# ts2068Interface.net
KiCad netlist of a schematic drawn in Altium Designer
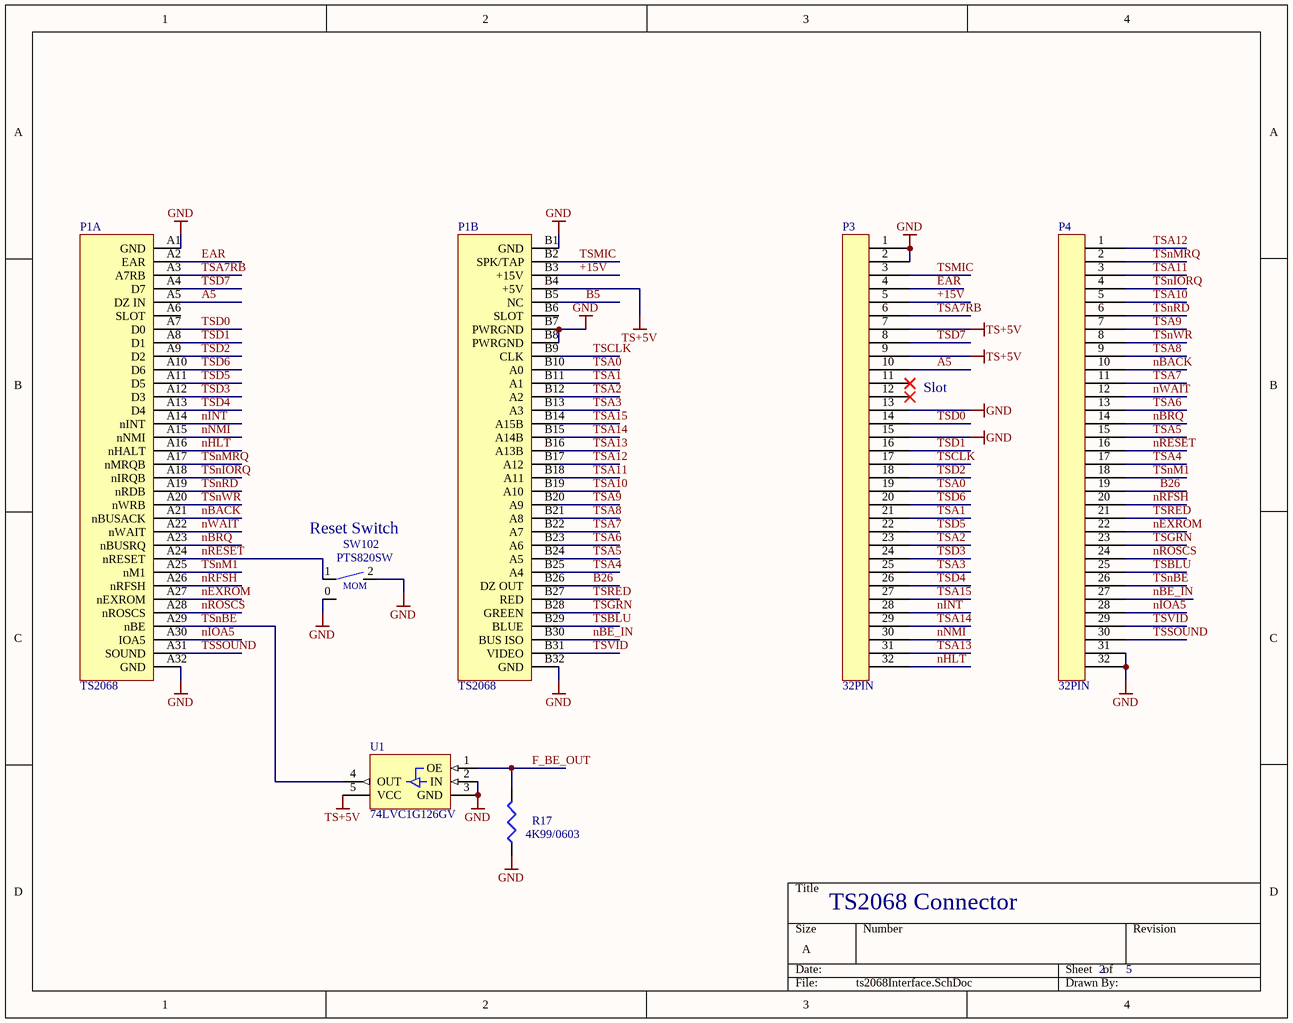
[diagram p0: ts2068Interface.SchDoc]

(export (version "E")
  (design (tool "Eeschema 10.0.6"))
  (components
    (comp (ref "P1") (value "TS2068") (footprint "TS2068A") (libsource (lib "Modules") (part "TS2068")))
    (comp (ref "P3") (value "32PIN") (footprint "IDC32") (libsource (lib "Connectors") (part "32PIN")))
    (comp (ref "P4") (value "32PIN") (footprint "IDC32") (libsource (lib "Connectors") (part "32PIN")))
    (comp (ref "R17")
      (value "4K99/0603")
      (footprint "0603")
      (description "RES 4.99K OHM 1/10W 1% 0603 SMD")
      (fields (field (name "MFG") "Dale/Vishay"))
      (libsource (lib "C64Interface") (part "4K99/0603"))
    )
    (comp (ref "SW102")
      (value "PTS820SW")
      (footprint "PTS820")
      (description "Tactile Switch SPST-NO Top Actuated Surface Mount")
      (fields (field (name "MFG") "C&K"))
      (libsource (lib "Misc") (part "PTS820SW"))
    )
    (comp (ref "U1")
      (value "74LVC1G126GV")
      (footprint "SOT23-5")
      (description "Buffer, Non-Inverting 1 Element 1 Bit per Element 3-State Output SC-74A")
      (fields (field (name "MFG") "Nexperia"))
      (libsource (lib "DigitalIC") (part "74LVC1G126GV"))
    )
  )
  (nets
    (net (code "1") (name "/+15V") (class "Default")
      (node (ref "P1") (pin "B3") (pinfunction "+15V_B3") (pintype "passive"))
      (node (ref "P3") (pin "5") (pintype "passive"))
    )
    (net (code "2") (name "/A5") (class "Default")
      (node (ref "P1") (pin "A5") (pinfunction "DZ_IN_A5") (pintype "passive"))
      (node (ref "P3") (pin "10") (pintype "passive"))
    )
    (net (code "3") (name "/B5") (class "Default")
      (node (ref "P1") (pin "B5") (pinfunction "NC_B5") (pintype "passive"))
    )
    (net (code "4") (name "/B26") (class "Default")
      (node (ref "P1") (pin "B26") (pinfunction "DZ_OUT_B26") (pintype "passive"))
      (node (ref "P4") (pin "19") (pintype "passive"))
    )
    (net (code "5") (name "/EAR") (class "Default")
      (node (ref "P1") (pin "A2") (pinfunction "EAR_A2") (pintype "passive"))
      (node (ref "P3") (pin "4") (pintype "passive"))
    )
    (net (code "6") (name "/F_BE_OUT") (class "Default")
      (node (ref "R17") (pin "2") (pintype "passive"))
      (node (ref "U1") (pin "1") (pinfunction "OE_1") (pintype "input"))
    )
    (net (code "7") (name "/TSA0") (class "Default")
      (node (ref "P1") (pin "B10") (pinfunction "A0_B10") (pintype "passive"))
      (node (ref "P3") (pin "19") (pintype "passive"))
    )
    (net (code "8") (name "/TSA1") (class "Default")
      (node (ref "P1") (pin "B11") (pinfunction "A1_B11") (pintype "passive"))
      (node (ref "P3") (pin "21") (pintype "passive"))
    )
    (net (code "9") (name "/TSA2") (class "Default")
      (node (ref "P1") (pin "B12") (pinfunction "A2_B12") (pintype "passive"))
      (node (ref "P3") (pin "23") (pintype "passive"))
    )
    (net (code "10") (name "/TSA3") (class "Default")
      (node (ref "P1") (pin "B13") (pinfunction "A3_B13") (pintype "passive"))
      (node (ref "P3") (pin "25") (pintype "passive"))
    )
    (net (code "11") (name "/TSA4") (class "Default")
      (node (ref "P1") (pin "B25") (pinfunction "A4_B25") (pintype "passive"))
      (node (ref "P4") (pin "17") (pintype "passive"))
    )
    (net (code "12") (name "/TSA5") (class "Default")
      (node (ref "P1") (pin "B24") (pinfunction "A5_B24") (pintype "passive"))
      (node (ref "P4") (pin "15") (pintype "passive"))
    )
    (net (code "13") (name "/TSA6") (class "Default")
      (node (ref "P1") (pin "B23") (pinfunction "A6_B23") (pintype "passive"))
      (node (ref "P4") (pin "13") (pintype "passive"))
    )
    (net (code "14") (name "/TSA7") (class "Default")
      (node (ref "P1") (pin "B22") (pinfunction "A7_B22") (pintype "passive"))
      (node (ref "P4") (pin "11") (pintype "passive"))
    )
    (net (code "15") (name "/TSA7RB") (class "Default")
      (node (ref "P1") (pin "A3") (pinfunction "A7RB_A3") (pintype "passive"))
      (node (ref "P3") (pin "6") (pintype "passive"))
    )
    (net (code "16") (name "/TSA8") (class "Default")
      (node (ref "P1") (pin "B21") (pinfunction "A8_B21") (pintype "passive"))
      (node (ref "P4") (pin "9") (pintype "passive"))
    )
    (net (code "17") (name "/TSA9") (class "Default")
      (node (ref "P1") (pin "B20") (pinfunction "A9_B20") (pintype "passive"))
      (node (ref "P4") (pin "7") (pintype "passive"))
    )
    (net (code "18") (name "/TSA10") (class "Default")
      (node (ref "P1") (pin "B19") (pinfunction "A10_B19") (pintype "passive"))
      (node (ref "P4") (pin "5") (pintype "passive"))
    )
    (net (code "19") (name "/TSA11") (class "Default")
      (node (ref "P1") (pin "B18") (pinfunction "A11_B18") (pintype "passive"))
      (node (ref "P4") (pin "3") (pintype "passive"))
    )
    (net (code "20") (name "/TSA12") (class "Default")
      (node (ref "P1") (pin "B17") (pinfunction "A12_B17") (pintype "passive"))
      (node (ref "P4") (pin "1") (pintype "passive"))
    )
    (net (code "21") (name "/TSA13") (class "Default")
      (node (ref "P1") (pin "B16") (pinfunction "A13B_B16") (pintype "passive"))
      (node (ref "P3") (pin "31") (pintype "passive"))
    )
    (net (code "22") (name "/TSA14") (class "Default")
      (node (ref "P1") (pin "B15") (pinfunction "A14B_B15") (pintype "passive"))
      (node (ref "P3") (pin "29") (pintype "passive"))
    )
    (net (code "23") (name "/TSA15") (class "Default")
      (node (ref "P1") (pin "B14") (pinfunction "A15B_B14") (pintype "passive"))
      (node (ref "P3") (pin "27") (pintype "passive"))
    )
    (net (code "24") (name "/TSBLU") (class "Default")
      (node (ref "P1") (pin "B29") (pinfunction "BLUE_B29") (pintype "passive"))
      (node (ref "P4") (pin "25") (pintype "passive"))
    )
    (net (code "25") (name "/TSCLK") (class "Default")
      (node (ref "P1") (pin "B9") (pinfunction "CLK_B9") (pintype "passive"))
      (node (ref "P3") (pin "17") (pintype "passive"))
    )
    (net (code "26") (name "/TSD0") (class "Default")
      (node (ref "P1") (pin "A7") (pinfunction "D0_A7") (pintype "passive"))
      (node (ref "P3") (pin "14") (pintype "passive"))
    )
    (net (code "27") (name "/TSD1") (class "Default")
      (node (ref "P1") (pin "A8") (pinfunction "D1_A8") (pintype "passive"))
      (node (ref "P3") (pin "16") (pintype "passive"))
    )
    (net (code "28") (name "/TSD2") (class "Default")
      (node (ref "P1") (pin "A9") (pinfunction "D2_A9") (pintype "passive"))
      (node (ref "P3") (pin "18") (pintype "passive"))
    )
    (net (code "29") (name "/TSD3") (class "Default")
      (node (ref "P1") (pin "A12") (pinfunction "D3_A12") (pintype "passive"))
      (node (ref "P3") (pin "24") (pintype "passive"))
    )
    (net (code "30") (name "/TSD4") (class "Default")
      (node (ref "P1") (pin "A13") (pinfunction "D4_A13") (pintype "passive"))
      (node (ref "P3") (pin "26") (pintype "passive"))
    )
    (net (code "31") (name "/TSD5") (class "Default")
      (node (ref "P1") (pin "A11") (pinfunction "D5_A11") (pintype "passive"))
      (node (ref "P3") (pin "22") (pintype "passive"))
    )
    (net (code "32") (name "/TSD6") (class "Default")
      (node (ref "P1") (pin "A10") (pinfunction "D6_A10") (pintype "passive"))
      (node (ref "P3") (pin "20") (pintype "passive"))
    )
    (net (code "33") (name "/TSD7") (class "Default")
      (node (ref "P1") (pin "A4") (pinfunction "D7_A4") (pintype "passive"))
      (node (ref "P3") (pin "8") (pintype "passive"))
    )
    (net (code "34") (name "/TSGRN") (class "Default")
      (node (ref "P1") (pin "B28") (pinfunction "GREEN_B28") (pintype "passive"))
      (node (ref "P4") (pin "23") (pintype "passive"))
    )
    (net (code "35") (name "/TSMIC") (class "Default")
      (node (ref "P1") (pin "B2") (pinfunction "SPK/TAP_B2") (pintype "passive"))
      (node (ref "P3") (pin "3") (pintype "passive"))
    )
    (net (code "36") (name "/TSRED") (class "Default")
      (node (ref "P1") (pin "B27") (pinfunction "RED_B27") (pintype "passive"))
      (node (ref "P4") (pin "21") (pintype "passive"))
    )
    (net (code "37") (name "/TSSOUND") (class "Default")
      (node (ref "P1") (pin "A31") (pinfunction "SOUND_A31") (pintype "passive"))
      (node (ref "P4") (pin "30") (pintype "passive"))
    )
    (net (code "38") (name "/TSVID") (class "Default")
      (node (ref "P1") (pin "B31") (pinfunction "VIDEO_B31") (pintype "passive"))
      (node (ref "P4") (pin "29") (pintype "passive"))
    )
    (net (code "39") (name "/TSnBE") (class "Default")
      (node (ref "P1") (pin "A29") (pinfunction "nBE_A29") (pintype "passive"))
      (node (ref "P4") (pin "26") (pintype "passive"))
      (node (ref "U1") (pin "4") (pinfunction "OUT_4") (pintype "output"))
    )
    (net (code "40") (name "/TSnIORQ") (class "Default")
      (node (ref "P1") (pin "A18") (pinfunction "nIRQB_A18") (pintype "passive"))
      (node (ref "P4") (pin "4") (pintype "passive"))
    )
    (net (code "41") (name "/TSnM1") (class "Default")
      (node (ref "P1") (pin "A25") (pinfunction "nM1_A25") (pintype "passive"))
      (node (ref "P4") (pin "18") (pintype "passive"))
    )
    (net (code "42") (name "/TSnMRQ") (class "Default")
      (node (ref "P1") (pin "A17") (pinfunction "nMRQB_A17") (pintype "passive"))
      (node (ref "P4") (pin "2") (pintype "passive"))
    )
    (net (code "43") (name "/TSnRD") (class "Default")
      (node (ref "P1") (pin "A19") (pinfunction "nRDB_A19") (pintype "passive"))
      (node (ref "P4") (pin "6") (pintype "passive"))
    )
    (net (code "44") (name "/TSnWR") (class "Default")
      (node (ref "P1") (pin "A20") (pinfunction "nWRB_A20") (pintype "passive"))
      (node (ref "P4") (pin "8") (pintype "passive"))
    )
    (net (code "45") (name "/nBACK") (class "Default")
      (node (ref "P1") (pin "A21") (pinfunction "nBUSACK_A21") (pintype "passive"))
      (node (ref "P4") (pin "10") (pintype "passive"))
    )
    (net (code "46") (name "/nBE_IN") (class "Default")
      (node (ref "P1") (pin "B30") (pinfunction "BUS_ISO_B30") (pintype "passive"))
      (node (ref "P4") (pin "27") (pintype "passive"))
    )
    (net (code "47") (name "/nBRQ") (class "Default")
      (node (ref "P1") (pin "A23") (pinfunction "nBUSRQ_A23") (pintype "passive"))
      (node (ref "P4") (pin "14") (pintype "passive"))
    )
    (net (code "48") (name "/nEXROM") (class "Default")
      (node (ref "P1") (pin "A27") (pinfunction "nEXROM_A27") (pintype "passive"))
      (node (ref "P4") (pin "22") (pintype "passive"))
    )
    (net (code "49") (name "/nHLT") (class "Default")
      (node (ref "P1") (pin "A16") (pinfunction "nHALT_A16") (pintype "passive"))
      (node (ref "P3") (pin "32") (pintype "passive"))
    )
    (net (code "50") (name "/nINT") (class "Default")
      (node (ref "P1") (pin "A14") (pinfunction "nINT_A14") (pintype "passive"))
      (node (ref "P3") (pin "28") (pintype "passive"))
    )
    (net (code "51") (name "/nIOA5") (class "Default")
      (node (ref "P1") (pin "A30") (pinfunction "IOA5_A30") (pintype "passive"))
      (node (ref "P4") (pin "28") (pintype "passive"))
    )
    (net (code "52") (name "/nNMI") (class "Default")
      (node (ref "P1") (pin "A15") (pinfunction "nNMI_A15") (pintype "passive"))
      (node (ref "P3") (pin "30") (pintype "passive"))
    )
    (net (code "53") (name "/nRESET") (class "Default")
      (node (ref "P1") (pin "A24") (pinfunction "nRESET_A24") (pintype "passive"))
      (node (ref "P4") (pin "16") (pintype "passive"))
      (node (ref "SW102") (pin "1") (pinfunction "1_1") (pintype "passive"))
    )
    (net (code "54") (name "/nRFSH") (class "Default")
      (node (ref "P1") (pin "A26") (pinfunction "nRFSH_A26") (pintype "passive"))
      (node (ref "P4") (pin "20") (pintype "passive"))
    )
    (net (code "55") (name "/nROSCS") (class "Default")
      (node (ref "P1") (pin "A28") (pinfunction "nROSCS_A28") (pintype "passive"))
      (node (ref "P4") (pin "24") (pintype "passive"))
    )
    (net (code "56") (name "/nWAIT") (class "Default")
      (node (ref "P1") (pin "A22") (pinfunction "nWAIT_A22") (pintype "passive"))
      (node (ref "P4") (pin "12") (pintype "passive"))
    )
    (net (code "57") (name "GND") (class "Default")
      (node (ref "P1") (pin "A1") (pinfunction "GND_A1") (pintype "passive"))
      (node (ref "P1") (pin "A32") (pinfunction "GND_A32") (pintype "passive"))
      (node (ref "P1") (pin "B1") (pinfunction "GND_B1") (pintype "passive"))
      (node (ref "P1") (pin "B32") (pinfunction "GND_B32") (pintype "passive"))
      (node (ref "P1") (pin "B7") (pinfunction "PWRGND_B7") (pintype "passive"))
      (node (ref "P1") (pin "B8") (pinfunction "PWRGND_B8") (pintype "passive"))
      (node (ref "P3") (pin "1") (pintype "passive"))
      (node (ref "P3") (pin "13") (pintype "passive"))
      (node (ref "P3") (pin "15") (pintype "passive"))
      (node (ref "P3") (pin "2") (pintype "passive"))
      (node (ref "P4") (pin "31") (pintype "passive"))
      (node (ref "P4") (pin "32") (pintype "passive"))
      (node (ref "R17") (pin "1") (pintype "passive"))
      (node (ref "SW102") (pin "0") (pinfunction "0_0") (pintype "passive"))
      (node (ref "SW102") (pin "2") (pinfunction "2_2") (pintype "passive"))
      (node (ref "U1") (pin "2") (pinfunction "IN_2") (pintype "input"))
      (node (ref "U1") (pin "3") (pinfunction "GND_3") (pintype "power_in"))
    )
    (net (code "58") (name "TS+5V") (class "Default")
      (node (ref "P1") (pin "B4") (pinfunction "+5V_B4") (pintype "passive"))
      (node (ref "P3") (pin "7") (pintype "passive"))
      (node (ref "P3") (pin "9") (pintype "passive"))
      (node (ref "U1") (pin "5") (pinfunction "VCC_5") (pintype "power_in"))
    )
    (net (code "59") (name "unconnected-(P1A-SLOT-PadA6)") (class "Default")
      (node (ref "P1") (pin "A6") (pinfunction "SLOT_A6") (pintype "passive"))
    )
    (net (code "60") (name "unconnected-(P1B-SLOT-PadB6)") (class "Default")
      (node (ref "P1") (pin "B6") (pinfunction "SLOT_B6") (pintype "passive"))
    )
    (net (code "61") (name "unconnected-(P3-Pad11)") (class "Default")
      (node (ref "P3") (pin "11") (pintype "passive+no_connect"))
    )
    (net (code "62") (name "unconnected-(P3-Pad12)") (class "Default")
      (node (ref "P3") (pin "12") (pintype "passive+no_connect"))
    )
  )
)
